# Tremolo.net
KiCad netlist of a schematic drawn in Altium Designer
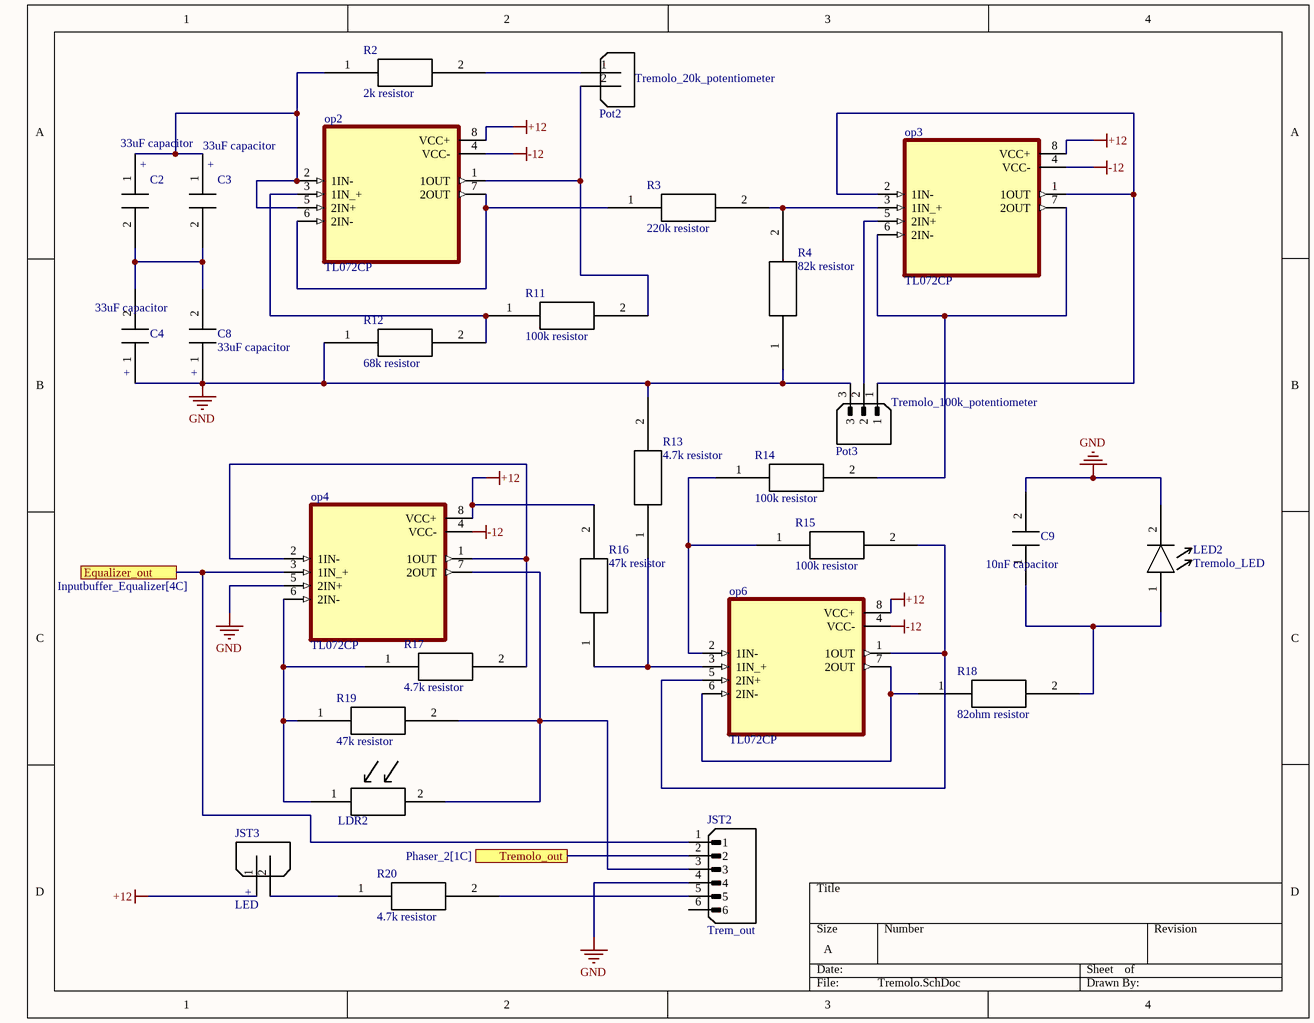
[diagram p0: Tremolo.SchDoc]

(export (version "E")
  (design (tool "Eeschema 10.0.6"))
  (components
    (comp (ref "C2")
      (value "33uF capacitor")
      (footprint "33uF")
      (libsource (lib "Analog_Project_Schlib") (part "33uF capacitor"))
    )
    (comp (ref "C3")
      (value "33uF capacitor")
      (footprint "33uF")
      (libsource (lib "Analog_Project_Schlib") (part "33uF capacitor"))
    )
    (comp (ref "C4")
      (value "33uF capacitor")
      (footprint "33uF")
      (libsource (lib "Analog_Project_Schlib") (part "33uF capacitor"))
    )
    (comp (ref "C8")
      (value "33uF capacitor")
      (footprint "33uF")
      (libsource (lib "Analog_Project_Schlib") (part "33uF capacitor"))
    )
    (comp (ref "C9")
      (value "10nF capacitor")
      (footprint "10nF")
      (libsource (lib "Analog_Project_Schlib") (part "10nF capacitor"))
    )
    (comp (ref "JST2")
      (value "Trem_out")
      (footprint "6pin_JST")
      (libsource (lib "Analog_Project_Schlib") (part "6pin_JST"))
    )
    (comp (ref "JST3")
      (value "LED")
      (footprint "2pin_JST")
      (libsource (lib "Analog_Project_Schlib") (part "2pin_JST"))
    )
    (comp (ref "LDR2") (value "LDR") (footprint "LDR") (libsource (lib "Analog_Project_Schlib") (part "LDR")))
    (comp (ref "LED2")
      (value "Tremolo_LED")
      (footprint "LED")
      (libsource (lib "Analog_Project_Schlib") (part "LED"))
    )
    (comp (ref "op2")
      (value "TL072CP")
      (footprint "TL072CP")
      (libsource (lib "Analog_Project_Schlib") (part "TL072CP"))
    )
    (comp (ref "op3")
      (value "TL072CP")
      (footprint "TL072CP")
      (libsource (lib "Analog_Project_Schlib") (part "TL072CP"))
    )
    (comp (ref "op4")
      (value "TL072CP")
      (footprint "TL072CP")
      (libsource (lib "Analog_Project_Schlib") (part "TL072CP"))
    )
    (comp (ref "op6")
      (value "TL072CP")
      (footprint "TL072CP")
      (libsource (lib "Analog_Project_Schlib") (part "TL072CP"))
    )
    (comp (ref "Pot2")
      (value "Tremolo_20k_potentiometer")
      (footprint "2pin_JST_non_polarized")
      (libsource (lib "Analog_Project_Schlib") (part "2pin_jst_non_polarized"))
    )
    (comp (ref "Pot3")
      (value "Tremolo_100k_potentiometer")
      (footprint "3pin_jst")
      (libsource (lib "Analog_Project_Schlib") (part "3pin_jst"))
    )
    (comp (ref "R2")
      (value "2k resistor")
      (footprint "2k")
      (libsource (lib "Analog_Project_Schlib") (part "2k resistor"))
    )
    (comp (ref "R3")
      (value "220k resistor")
      (footprint "220k")
      (libsource (lib "Analog_Project_Schlib") (part "220k resistor"))
    )
    (comp (ref "R4")
      (value "82k resistor")
      (footprint "82k")
      (libsource (lib "Analog_Project_Schlib") (part "82k resistor"))
    )
    (comp (ref "R11")
      (value "100k resistor")
      (footprint "100k")
      (libsource (lib "Analog_Project_Schlib") (part "100k resistor"))
    )
    (comp (ref "R12")
      (value "68k resistor")
      (footprint "68k")
      (libsource (lib "Analog_Project_Schlib") (part "68k resistor"))
    )
    (comp (ref "R13")
      (value "4.7k resistor")
      (footprint "4.7k")
      (libsource (lib "Analog_Project_Schlib") (part "4.7k resistor"))
    )
    (comp (ref "R14")
      (value "100k resistor")
      (footprint "100k")
      (libsource (lib "Analog_Project_Schlib") (part "100k resistor"))
    )
    (comp (ref "R15")
      (value "100k resistor")
      (footprint "100k")
      (libsource (lib "Analog_Project_Schlib") (part "100k resistor"))
    )
    (comp (ref "R16")
      (value "47k resistor")
      (footprint "47k")
      (libsource (lib "Analog_Project_Schlib") (part "47k resistor"))
    )
    (comp (ref "R17")
      (value "4.7k resistor")
      (footprint "4.7k")
      (libsource (lib "Analog_Project_Schlib") (part "4.7k resistor"))
    )
    (comp (ref "R18")
      (value "82ohm resistor")
      (footprint "82")
      (libsource (lib "Analog_Project_Schlib") (part "82ohm resistor"))
    )
    (comp (ref "R19")
      (value "47k resistor")
      (footprint "47k")
      (libsource (lib "Analog_Project_Schlib") (part "47k resistor"))
    )
    (comp (ref "R20")
      (value "4.7k resistor")
      (footprint "4.7k")
      (libsource (lib "Analog_Project_Schlib") (part "4.7k resistor"))
    )
  )
  (nets
    (net (code "1") (name "+12") (class "Default")
      (node (ref "JST3") (pin "1") (pinfunction "1_1") (pintype "passive"))
      (node (ref "R16") (pin "2") (pinfunction "2_2") (pintype "passive"))
      (node (ref "op2") (pin "8") (pinfunction "VCC+_8") (pintype "power_in"))
      (node (ref "op3") (pin "8") (pinfunction "VCC+_8") (pintype "power_in"))
      (node (ref "op4") (pin "8") (pinfunction "VCC+_8") (pintype "power_in"))
      (node (ref "op6") (pin "8") (pinfunction "VCC+_8") (pintype "power_in"))
    )
    (net (code "2") (name "-12") (class "Default")
      (node (ref "op2") (pin "4") (pinfunction "VCC-_4") (pintype "power_in"))
      (node (ref "op3") (pin "4") (pinfunction "VCC-_4") (pintype "power_in"))
      (node (ref "op4") (pin "4") (pinfunction "VCC-_4") (pintype "power_in"))
      (node (ref "op6") (pin "4") (pinfunction "VCC-_4") (pintype "power_in"))
    )
    (net (code "3") (name "/Equalizer_out") (class "Default")
      (node (ref "JST2") (pin "1") (pinfunction "1_1") (pintype "passive"))
      (node (ref "op4") (pin "3") (pinfunction "1IN_+_3") (pintype "input"))
    )
    (net (code "4") (name "/Tremolo_out") (class "Default")
      (node (ref "JST2") (pin "2") (pinfunction "2_2") (pintype "passive"))
    )
    (net (code "5") (name "GND") (class "Default")
      (node (ref "C4") (pin "1") (pinfunction "1_1") (pintype "passive"))
      (node (ref "C8") (pin "1") (pinfunction "1_1") (pintype "passive"))
      (node (ref "C9") (pin "2") (pinfunction "2_2") (pintype "passive"))
      (node (ref "JST2") (pin "4") (pinfunction "4_4") (pintype "passive"))
      (node (ref "LED2") (pin "2") (pinfunction "2_2") (pintype "passive"))
      (node (ref "Pot3") (pin "3") (pinfunction "3_3") (pintype "passive"))
      (node (ref "R12") (pin "1") (pinfunction "1_1") (pintype "passive"))
      (node (ref "R13") (pin "2") (pinfunction "2_2") (pintype "passive"))
      (node (ref "R4") (pin "1") (pinfunction "1_1") (pintype "passive"))
      (node (ref "op4") (pin "5") (pinfunction "2IN+_5") (pintype "input"))
    )
    (net (code "6") (name "Net-(C2-Pad2)") (class "Default")
      (node (ref "C2") (pin "2") (pinfunction "2_2") (pintype "passive"))
      (node (ref "C3") (pin "2") (pinfunction "2_2") (pintype "passive"))
      (node (ref "C4") (pin "2") (pinfunction "2_2") (pintype "passive"))
      (node (ref "C8") (pin "2") (pinfunction "2_2") (pintype "passive"))
    )
    (net (code "7") (name "Net-(C9-Pad1)") (class "Default")
      (node (ref "C9") (pin "1") (pinfunction "1_1") (pintype "passive"))
      (node (ref "LED2") (pin "1") (pinfunction "1_1") (pintype "passive"))
      (node (ref "R18") (pin "2") (pinfunction "2_2") (pintype "passive"))
    )
    (net (code "8") (name "Net-(JST2-Pad5)") (class "Default")
      (node (ref "JST2") (pin "5") (pinfunction "5_5") (pintype "passive"))
      (node (ref "R20") (pin "2") (pinfunction "2_2") (pintype "passive"))
    )
    (net (code "9") (name "Net-(JST3-Pad2)") (class "Default")
      (node (ref "JST3") (pin "2") (pinfunction "2_2") (pintype "passive"))
      (node (ref "R20") (pin "1") (pinfunction "1_1") (pintype "passive"))
    )
    (net (code "10") (name "Net-(Pot2-Pad1)") (class "Default")
      (node (ref "Pot2") (pin "1") (pinfunction "1_1") (pintype "passive"))
      (node (ref "R2") (pin "2") (pinfunction "2_2") (pintype "passive"))
    )
    (net (code "11") (name "Net-(op2-1IN-)") (class "Default")
      (node (ref "C2") (pin "1") (pinfunction "1_1") (pintype "passive"))
      (node (ref "C3") (pin "1") (pinfunction "1_1") (pintype "passive"))
      (node (ref "R2") (pin "1") (pinfunction "1_1") (pintype "passive"))
      (node (ref "op2") (pin "2") (pinfunction "1IN-_2") (pintype "input"))
      (node (ref "op2") (pin "5") (pinfunction "2IN+_5") (pintype "input"))
    )
    (net (code "12") (name "Net-(op2-1IN_+)") (class "Default")
      (node (ref "R11") (pin "1") (pinfunction "1_1") (pintype "passive"))
      (node (ref "R12") (pin "2") (pinfunction "2_2") (pintype "passive"))
      (node (ref "op2") (pin "3") (pinfunction "1IN_+_3") (pintype "input"))
    )
    (net (code "13") (name "Net-(op2-1OUT)") (class "Default")
      (node (ref "Pot2") (pin "2") (pinfunction "2_2") (pintype "passive"))
      (node (ref "R11") (pin "2") (pinfunction "2_2") (pintype "passive"))
      (node (ref "op2") (pin "1") (pinfunction "1OUT_1") (pintype "output"))
    )
    (net (code "14") (name "Net-(op2-2IN-)") (class "Default")
      (node (ref "R3") (pin "1") (pinfunction "1_1") (pintype "passive"))
      (node (ref "op2") (pin "6") (pinfunction "2IN-_6") (pintype "input"))
      (node (ref "op2") (pin "7") (pinfunction "2OUT_7") (pintype "output"))
    )
    (net (code "15") (name "Net-(op3-1IN-)") (class "Default")
      (node (ref "Pot3") (pin "1") (pinfunction "1_1") (pintype "passive"))
      (node (ref "op3") (pin "1") (pinfunction "1OUT_1") (pintype "output"))
      (node (ref "op3") (pin "2") (pinfunction "1IN-_2") (pintype "input"))
    )
    (net (code "16") (name "Net-(op3-1IN_+)") (class "Default")
      (node (ref "R3") (pin "2") (pinfunction "2_2") (pintype "passive"))
      (node (ref "R4") (pin "2") (pinfunction "2_2") (pintype "passive"))
      (node (ref "op3") (pin "3") (pinfunction "1IN_+_3") (pintype "input"))
    )
    (net (code "17") (name "Net-(op3-2IN+)") (class "Default")
      (node (ref "Pot3") (pin "2") (pinfunction "2_2") (pintype "passive"))
      (node (ref "op3") (pin "5") (pinfunction "2IN+_5") (pintype "input"))
    )
    (net (code "18") (name "Net-(op3-2IN-)") (class "Default")
      (node (ref "R14") (pin "2") (pinfunction "2_2") (pintype "passive"))
      (node (ref "op3") (pin "6") (pinfunction "2IN-_6") (pintype "input"))
      (node (ref "op3") (pin "7") (pinfunction "2OUT_7") (pintype "output"))
    )
    (net (code "19") (name "Net-(op4-1IN-)") (class "Default")
      (node (ref "R17") (pin "2") (pinfunction "2_2") (pintype "passive"))
      (node (ref "op4") (pin "1") (pinfunction "1OUT_1") (pintype "output"))
      (node (ref "op4") (pin "2") (pinfunction "1IN-_2") (pintype "input"))
    )
    (net (code "20") (name "Net-(op4-2IN-)") (class "Default")
      (node (ref "LDR2") (pin "1") (pinfunction "1_1") (pintype "passive"))
      (node (ref "R17") (pin "1") (pinfunction "1_1") (pintype "passive"))
      (node (ref "R19") (pin "1") (pinfunction "1_1") (pintype "passive"))
      (node (ref "op4") (pin "6") (pinfunction "2IN-_6") (pintype "input"))
    )
    (net (code "21") (name "Net-(op4-2OUT)") (class "Default")
      (node (ref "JST2") (pin "3") (pinfunction "3_3") (pintype "passive"))
      (node (ref "LDR2") (pin "2") (pinfunction "2_2") (pintype "passive"))
      (node (ref "R19") (pin "2") (pinfunction "2_2") (pintype "passive"))
      (node (ref "op4") (pin "7") (pinfunction "2OUT_7") (pintype "output"))
    )
    (net (code "22") (name "Net-(op6-1IN-)") (class "Default")
      (node (ref "R14") (pin "1") (pinfunction "1_1") (pintype "passive"))
      (node (ref "R15") (pin "1") (pinfunction "1_1") (pintype "passive"))
      (node (ref "op6") (pin "2") (pinfunction "1IN-_2") (pintype "input"))
    )
    (net (code "23") (name "Net-(op6-1IN_+)") (class "Default")
      (node (ref "R13") (pin "1") (pinfunction "1_1") (pintype "passive"))
      (node (ref "R16") (pin "1") (pinfunction "1_1") (pintype "passive"))
      (node (ref "op6") (pin "3") (pinfunction "1IN_+_3") (pintype "input"))
    )
    (net (code "24") (name "Net-(op6-1OUT)") (class "Default")
      (node (ref "R15") (pin "2") (pinfunction "2_2") (pintype "passive"))
      (node (ref "op6") (pin "1") (pinfunction "1OUT_1") (pintype "output"))
      (node (ref "op6") (pin "5") (pinfunction "2IN+_5") (pintype "input"))
    )
    (net (code "25") (name "Net-(op6-2IN-)") (class "Default")
      (node (ref "R18") (pin "1") (pinfunction "1_1") (pintype "passive"))
      (node (ref "op6") (pin "6") (pinfunction "2IN-_6") (pintype "input"))
      (node (ref "op6") (pin "7") (pinfunction "2OUT_7") (pintype "output"))
    )
    (net (code "26") (name "unconnected-(JST2-Pad6)") (class "Default")
      (node (ref "JST2") (pin "6") (pinfunction "6_6") (pintype "passive"))
    )
  )
)
